# Robot.net
KiCad netlist of a schematic drawn in EAGLE
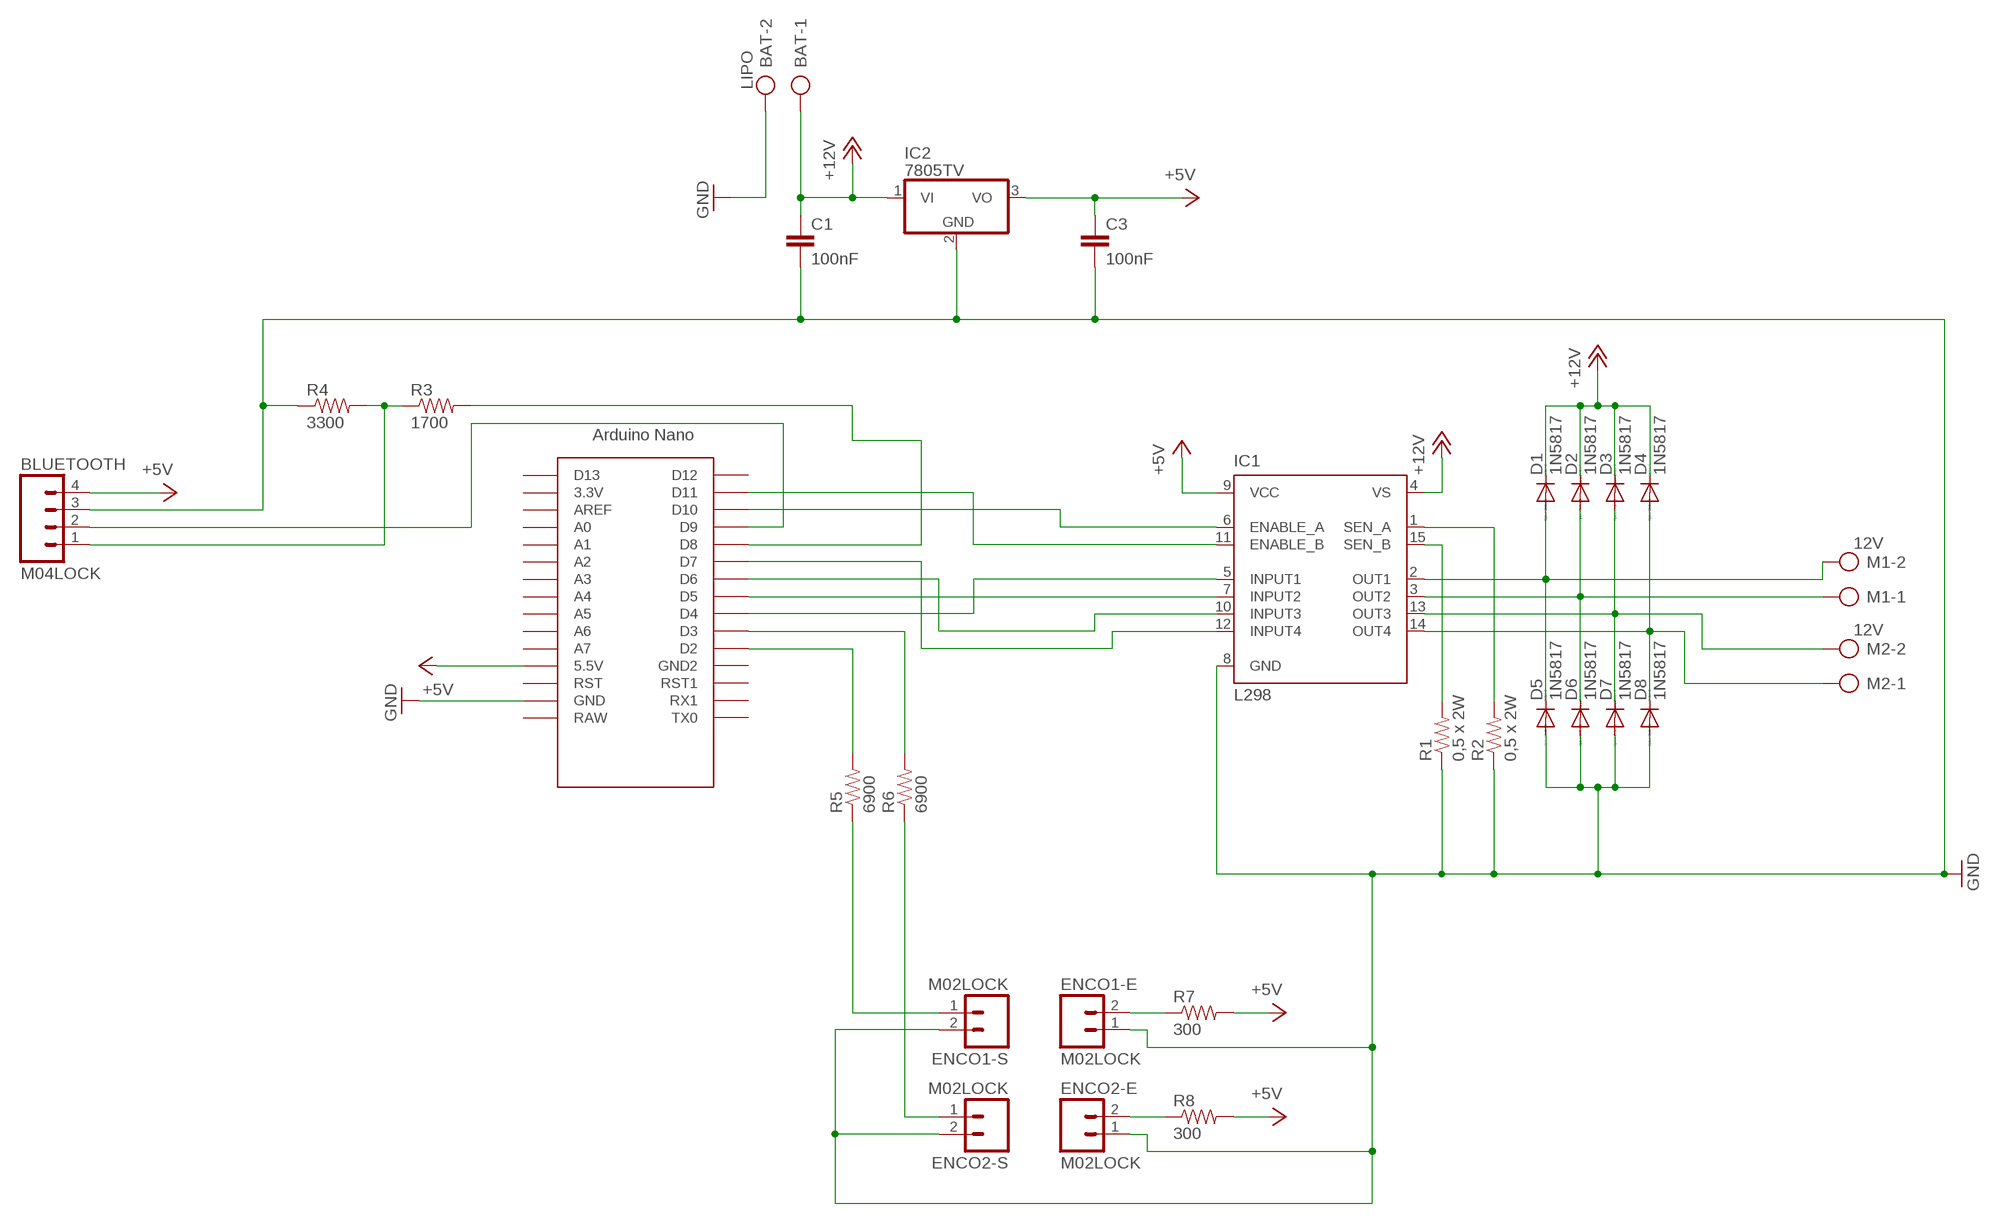
[diagram p0: schematic, sheet 1]

(export (version "E")
  (design (tool "Eeschema 10.0.6"))
  (components
    (comp (ref "BAT")
      (value "LIPO")
      (footprint "eagle-import:AK500_2-H")
      (libsource (lib "eagle-import") (part "AK500/2-H"))
    )
    (comp (ref "BLUETOOTH")
      (value "M04LOCK")
      (footprint "eagle-import:1X04_LOCK")
      (libsource (lib "eagle-import") (part "M04LOCK"))
    )
    (comp (ref "C1")
      (value "100nF")
      (footprint "eagle-import:C050-025X075")
      (libsource (lib "eagle-import") (part "C-EU050-025X075"))
    )
    (comp (ref "C3")
      (value "100nF")
      (footprint "eagle-import:C050-025X075")
      (libsource (lib "eagle-import") (part "C-EU050-025X075"))
    )
    (comp (ref "D1")
      (value "1N5817")
      (footprint "eagle-import:DO41-10")
      (libsource (lib "eagle-import") (part "1N4004"))
    )
    (comp (ref "D2")
      (value "1N5817")
      (footprint "eagle-import:DO41-10")
      (libsource (lib "eagle-import") (part "1N4004"))
    )
    (comp (ref "D3")
      (value "1N5817")
      (footprint "eagle-import:DO41-10")
      (libsource (lib "eagle-import") (part "1N4004"))
    )
    (comp (ref "D4")
      (value "1N5817")
      (footprint "eagle-import:DO41-10")
      (libsource (lib "eagle-import") (part "1N4004"))
    )
    (comp (ref "D5")
      (value "1N5817")
      (footprint "eagle-import:DO41-10")
      (libsource (lib "eagle-import") (part "1N4004"))
    )
    (comp (ref "D6")
      (value "1N5817")
      (footprint "eagle-import:DO41-10")
      (libsource (lib "eagle-import") (part "1N4004"))
    )
    (comp (ref "D7")
      (value "1N5817")
      (footprint "eagle-import:DO41-10")
      (libsource (lib "eagle-import") (part "1N4004"))
    )
    (comp (ref "D8")
      (value "1N5817")
      (footprint "eagle-import:DO41-10")
      (libsource (lib "eagle-import") (part "1N4004"))
    )
    (comp (ref "ENCO1-E")
      (value "M02LOCK")
      (footprint "eagle-import:1X02_LOCK")
      (libsource (lib "eagle-import") (part "M02LOCK"))
    )
    (comp (ref "ENCO1-S")
      (value "M02LOCK")
      (footprint "eagle-import:1X02_LOCK")
      (libsource (lib "eagle-import") (part "M02LOCK"))
    )
    (comp (ref "ENCO2-E")
      (value "M02LOCK")
      (footprint "eagle-import:1X02_LOCK")
      (libsource (lib "eagle-import") (part "M02LOCK"))
    )
    (comp (ref "ENCO2-S")
      (value "M02LOCK")
      (footprint "eagle-import:1X02_LOCK")
      (libsource (lib "eagle-import") (part "M02LOCK"))
    )
    (comp (ref "IC1")
      (value "L298")
      (footprint "eagle-import:MULTIWATT-15")
      (fields (field (name "MPN") "L298N"))
      (libsource (lib "eagle-import") (part "L298"))
    )
    (comp (ref "IC2")
      (value "7805TV")
      (footprint "eagle-import:TO220V")
      (libsource (lib "eagle-import") (part "78TV05"))
    )
    (comp (ref "M1")
      (value "12V")
      (footprint "eagle-import:AK500_2-H")
      (libsource (lib "eagle-import") (part "AK500/2-H"))
    )
    (comp (ref "M2")
      (value "12V")
      (footprint "eagle-import:AK500_2-H")
      (libsource (lib "eagle-import") (part "AK500/2-H"))
    )
    (comp (ref "R1")
      (value "0,5 x 2W")
      (footprint "eagle-import:AXIAL-0.5")
      (libsource (lib "eagle-import") (part "RESISTORPTH-1/2W"))
    )
    (comp (ref "R2")
      (value "0,5 x 2W")
      (footprint "eagle-import:AXIAL-0.5")
      (libsource (lib "eagle-import") (part "RESISTORPTH-1/2W"))
    )
    (comp (ref "R3")
      (value "1700")
      (footprint "eagle-import:AXIAL-0.3")
      (libsource (lib "eagle-import") (part "RESISTORAXIAL-0.3"))
    )
    (comp (ref "R4")
      (value "3300")
      (footprint "eagle-import:AXIAL-0.3")
      (libsource (lib "eagle-import") (part "RESISTORAXIAL-0.3"))
    )
    (comp (ref "R5")
      (value "6900")
      (footprint "eagle-import:AXIAL-0.3")
      (libsource (lib "eagle-import") (part "RESISTORAXIAL-0.3"))
    )
    (comp (ref "R6")
      (value "6900")
      (footprint "eagle-import:AXIAL-0.3")
      (libsource (lib "eagle-import") (part "RESISTORAXIAL-0.3"))
    )
    (comp (ref "R7")
      (value "300")
      (footprint "eagle-import:AXIAL-0.3")
      (libsource (lib "eagle-import") (part "RESISTORAXIAL-0.3"))
    )
    (comp (ref "R8")
      (value "300")
      (footprint "eagle-import:AXIAL-0.3")
      (libsource (lib "eagle-import") (part "RESISTORAXIAL-0.3"))
    )
    (comp (ref "U$1")
      (value "NANO")
      (footprint "eagle-import:NANO")
      (libsource (lib "eagle-import") (part "NANO"))
    )
  )
  (nets
    (net (code "1") (name "+5V") (class "Default")
      (node (ref "BLUETOOTH") (pin "4") (pinfunction "4_4") (pintype "passive"))
      (node (ref "C3") (pin "1") (pinfunction "1_1") (pintype "passive"))
      (node (ref "IC1") (pin "9") (pinfunction "VCC_9") (pintype "power_in"))
      (node (ref "IC2") (pin "3") (pinfunction "VO_3") (pintype "passive"))
      (node (ref "R7") (pin "P$2") (pinfunction "2_P$2") (pintype "passive"))
      (node (ref "R8") (pin "P$2") (pinfunction "2_P$2") (pintype "passive"))
      (node (ref "U$1") (pin "5V") (pinfunction "5.5V_5V") (pintype "bidirectional"))
    )
    (net (code "2") (name "+12V") (class "Default")
      (node (ref "BAT") (pin "1") (pinfunction "KL_1") (pintype "passive"))
      (node (ref "C1") (pin "1") (pinfunction "1_1") (pintype "passive"))
      (node (ref "D1") (pin "C") (pinfunction "C_C") (pintype "passive"))
      (node (ref "D2") (pin "C") (pinfunction "C_C") (pintype "passive"))
      (node (ref "D3") (pin "C") (pinfunction "C_C") (pintype "passive"))
      (node (ref "D4") (pin "C") (pinfunction "C_C") (pintype "passive"))
      (node (ref "IC1") (pin "4") (pinfunction "VS_4") (pintype "power_in"))
      (node (ref "IC2") (pin "1") (pinfunction "VI_1") (pintype "input"))
    )
    (net (code "3") (name "GND") (class "Default")
      (node (ref "BAT") (pin "2") (pinfunction "KL_2") (pintype "passive"))
      (node (ref "BLUETOOTH") (pin "3") (pinfunction "3_3") (pintype "passive"))
      (node (ref "C1") (pin "2") (pinfunction "2_2") (pintype "passive"))
      (node (ref "C3") (pin "2") (pinfunction "2_2") (pintype "passive"))
      (node (ref "D5") (pin "A") (pinfunction "A_A") (pintype "passive"))
      (node (ref "D6") (pin "A") (pinfunction "A_A") (pintype "passive"))
      (node (ref "D7") (pin "A") (pinfunction "A_A") (pintype "passive"))
      (node (ref "D8") (pin "A") (pinfunction "A_A") (pintype "passive"))
      (node (ref "ENCO1-E") (pin "1") (pinfunction "1_1") (pintype "passive"))
      (node (ref "ENCO1-S") (pin "2") (pinfunction "2_2") (pintype "passive"))
      (node (ref "ENCO2-E") (pin "1") (pinfunction "1_1") (pintype "passive"))
      (node (ref "ENCO2-S") (pin "2") (pinfunction "2_2") (pintype "passive"))
      (node (ref "IC1") (pin "8") (pinfunction "GND_8") (pintype "power_in"))
      (node (ref "IC2") (pin "2") (pinfunction "GND_2") (pintype "passive"))
      (node (ref "R1") (pin "P$1") (pinfunction "1_P$1") (pintype "passive"))
      (node (ref "R2") (pin "P$1") (pinfunction "1_P$1") (pintype "passive"))
      (node (ref "R4") (pin "P$1") (pinfunction "1_P$1") (pintype "passive"))
      (node (ref "U$1") (pin "GND") (pinfunction "GND_GND") (pintype "bidirectional"))
    )
    (net (code "4") (name "Net-(BLUETOOTH-Pad2)") (class "Default")
      (node (ref "BLUETOOTH") (pin "2") (pinfunction "2_2") (pintype "passive"))
      (node (ref "U$1") (pin "D9") (pinfunction "D9_D9") (pintype "bidirectional"))
    )
    (net (code "5") (name "Net-(IC1-ENABLE_A)") (class "Default")
      (node (ref "IC1") (pin "6") (pinfunction "ENABLE_A_6") (pintype "input"))
      (node (ref "U$1") (pin "D10") (pinfunction "D10_D10") (pintype "bidirectional"))
    )
    (net (code "6") (name "Net-(IC1-ENABLE_B)") (class "Default")
      (node (ref "IC1") (pin "11") (pinfunction "ENABLE_B_11") (pintype "input"))
      (node (ref "U$1") (pin "D11") (pinfunction "D11_D11") (pintype "bidirectional"))
    )
    (net (code "7") (name "Net-(IC1-INPUT1)") (class "Default")
      (node (ref "IC1") (pin "5") (pinfunction "INPUT1_5") (pintype "input"))
      (node (ref "U$1") (pin "D4") (pinfunction "D4_D4") (pintype "bidirectional"))
    )
    (net (code "8") (name "Net-(IC1-INPUT2)") (class "Default")
      (node (ref "IC1") (pin "7") (pinfunction "INPUT2_7") (pintype "input"))
      (node (ref "U$1") (pin "D5") (pinfunction "D5_D5") (pintype "bidirectional"))
    )
    (net (code "9") (name "Net-(IC1-INPUT3)") (class "Default")
      (node (ref "IC1") (pin "10") (pinfunction "INPUT3_10") (pintype "input"))
      (node (ref "U$1") (pin "D6") (pinfunction "D6_D6") (pintype "bidirectional"))
    )
    (net (code "10") (name "Net-(IC1-INPUT4)") (class "Default")
      (node (ref "IC1") (pin "12") (pinfunction "INPUT4_12") (pintype "input"))
      (node (ref "U$1") (pin "D7") (pinfunction "D7_D7") (pintype "bidirectional"))
    )
    (net (code "11") (name "Net-(IC1-OUT1)") (class "Default")
      (node (ref "D1") (pin "A") (pinfunction "A_A") (pintype "passive"))
      (node (ref "D5") (pin "C") (pinfunction "C_C") (pintype "passive"))
      (node (ref "IC1") (pin "2") (pinfunction "OUT1_2") (pintype "output"))
      (node (ref "M1") (pin "2") (pinfunction "KL_2") (pintype "passive"))
    )
    (net (code "12") (name "Net-(IC1-OUT2)") (class "Default")
      (node (ref "D2") (pin "A") (pinfunction "A_A") (pintype "passive"))
      (node (ref "D6") (pin "C") (pinfunction "C_C") (pintype "passive"))
      (node (ref "IC1") (pin "3") (pinfunction "OUT2_3") (pintype "output"))
      (node (ref "M1") (pin "1") (pinfunction "KL_1") (pintype "passive"))
    )
    (net (code "13") (name "Net-(IC1-OUT3)") (class "Default")
      (node (ref "D3") (pin "A") (pinfunction "A_A") (pintype "passive"))
      (node (ref "D7") (pin "C") (pinfunction "C_C") (pintype "passive"))
      (node (ref "IC1") (pin "13") (pinfunction "OUT3_13") (pintype "output"))
      (node (ref "M2") (pin "2") (pinfunction "KL_2") (pintype "passive"))
    )
    (net (code "14") (name "Net-(IC1-OUT4)") (class "Default")
      (node (ref "D4") (pin "A") (pinfunction "A_A") (pintype "passive"))
      (node (ref "D8") (pin "C") (pinfunction "C_C") (pintype "passive"))
      (node (ref "IC1") (pin "14") (pinfunction "OUT4_14") (pintype "output"))
      (node (ref "M2") (pin "1") (pinfunction "KL_1") (pintype "passive"))
    )
    (net (code "15") (name "Net-(IC1-SEN_A)") (class "Default")
      (node (ref "IC1") (pin "1") (pinfunction "SEN_A_1") (pintype "input"))
      (node (ref "R2") (pin "P$2") (pinfunction "2_P$2") (pintype "passive"))
    )
    (net (code "16") (name "Net-(IC1-SEN_B)") (class "Default")
      (node (ref "IC1") (pin "15") (pinfunction "SEN_B_15") (pintype "input"))
      (node (ref "R1") (pin "P$2") (pinfunction "2_P$2") (pintype "passive"))
    )
    (net (code "17") (name "Net-(R3-1)") (class "Default")
      (node (ref "BLUETOOTH") (pin "1") (pinfunction "1_1") (pintype "passive"))
      (node (ref "R3") (pin "P$1") (pinfunction "1_P$1") (pintype "passive"))
      (node (ref "R4") (pin "P$2") (pinfunction "2_P$2") (pintype "passive"))
    )
    (net (code "18") (name "Net-(R3-2)") (class "Default")
      (node (ref "R3") (pin "P$2") (pinfunction "2_P$2") (pintype "passive"))
      (node (ref "U$1") (pin "D8") (pinfunction "D8_D8") (pintype "bidirectional"))
    )
    (net (code "19") (name "Net-(R5-1)") (class "Default")
      (node (ref "ENCO1-S") (pin "1") (pinfunction "1_1") (pintype "passive"))
      (node (ref "R5") (pin "P$1") (pinfunction "1_P$1") (pintype "passive"))
    )
    (net (code "20") (name "Net-(R5-2)") (class "Default")
      (node (ref "R5") (pin "P$2") (pinfunction "2_P$2") (pintype "passive"))
      (node (ref "U$1") (pin "D2") (pinfunction "D2_D2") (pintype "bidirectional"))
    )
    (net (code "21") (name "Net-(R6-1)") (class "Default")
      (node (ref "ENCO2-S") (pin "1") (pinfunction "1_1") (pintype "passive"))
      (node (ref "R6") (pin "P$1") (pinfunction "1_P$1") (pintype "passive"))
    )
    (net (code "22") (name "Net-(R6-2)") (class "Default")
      (node (ref "R6") (pin "P$2") (pinfunction "2_P$2") (pintype "passive"))
      (node (ref "U$1") (pin "D3") (pinfunction "D3_D3") (pintype "bidirectional"))
    )
    (net (code "23") (name "Net-(R7-1)") (class "Default")
      (node (ref "ENCO1-E") (pin "2") (pinfunction "2_2") (pintype "passive"))
      (node (ref "R7") (pin "P$1") (pinfunction "1_P$1") (pintype "passive"))
    )
    (net (code "24") (name "Net-(R8-1)") (class "Default")
      (node (ref "ENCO2-E") (pin "2") (pinfunction "2_2") (pintype "passive"))
      (node (ref "R8") (pin "P$1") (pinfunction "1_P$1") (pintype "passive"))
    )
    (net (code "25") (name "unconnected-(U$1-GND2-PadGND1)") (class "Default")
      (node (ref "U$1") (pin "GND1") (pinfunction "GND2_GND1") (pintype "bidirectional"))
    )
    (net (code "26") (name "unconnected-(U$1-Pad3.3V)") (class "Default")
      (node (ref "U$1") (pin "3.3V") (pinfunction "3.3V_3.3V") (pintype "bidirectional"))
    )
    (net (code "27") (name "unconnected-(U$1-PadA0)") (class "Default")
      (node (ref "U$1") (pin "A0") (pinfunction "A0_A0") (pintype "bidirectional"))
    )
    (net (code "28") (name "unconnected-(U$1-PadA1)") (class "Default")
      (node (ref "U$1") (pin "A1") (pinfunction "A1_A1") (pintype "bidirectional"))
    )
    (net (code "29") (name "unconnected-(U$1-PadA2)") (class "Default")
      (node (ref "U$1") (pin "A2") (pinfunction "A2_A2") (pintype "bidirectional"))
    )
    (net (code "30") (name "unconnected-(U$1-PadA3)") (class "Default")
      (node (ref "U$1") (pin "A3") (pinfunction "A3_A3") (pintype "bidirectional"))
    )
    (net (code "31") (name "unconnected-(U$1-PadA4)") (class "Default")
      (node (ref "U$1") (pin "A4") (pinfunction "A4_A4") (pintype "bidirectional"))
    )
    (net (code "32") (name "unconnected-(U$1-PadA5)") (class "Default")
      (node (ref "U$1") (pin "A5") (pinfunction "A5_A5") (pintype "bidirectional"))
    )
    (net (code "33") (name "unconnected-(U$1-PadA6)") (class "Default")
      (node (ref "U$1") (pin "A6") (pinfunction "A6_A6") (pintype "bidirectional"))
    )
    (net (code "34") (name "unconnected-(U$1-PadA7)") (class "Default")
      (node (ref "U$1") (pin "A7") (pinfunction "A7_A7") (pintype "bidirectional"))
    )
    (net (code "35") (name "unconnected-(U$1-PadAREF)") (class "Default")
      (node (ref "U$1") (pin "AREF") (pinfunction "AREF_AREF") (pintype "bidirectional"))
    )
    (net (code "36") (name "unconnected-(U$1-PadD12)") (class "Default")
      (node (ref "U$1") (pin "D12") (pinfunction "D12_D12") (pintype "bidirectional"))
    )
    (net (code "37") (name "unconnected-(U$1-PadD13)") (class "Default")
      (node (ref "U$1") (pin "D13") (pinfunction "D13_D13") (pintype "bidirectional"))
    )
    (net (code "38") (name "unconnected-(U$1-PadICSP1)") (class "Default")
      (node (ref "U$1") (pin "ICSP1") (pinfunction "ICSP1_ICSP1") (pintype "bidirectional"))
    )
    (net (code "39") (name "unconnected-(U$1-PadICSP2)") (class "Default")
      (node (ref "U$1") (pin "ICSP2") (pinfunction "ICSP2_ICSP2") (pintype "bidirectional"))
    )
    (net (code "40") (name "unconnected-(U$1-PadICSP3)") (class "Default")
      (node (ref "U$1") (pin "ICSP3") (pinfunction "ICSP3_ICSP3") (pintype "bidirectional"))
    )
    (net (code "41") (name "unconnected-(U$1-PadICSP4)") (class "Default")
      (node (ref "U$1") (pin "ICSP4") (pinfunction "ICSP4_ICSP4") (pintype "bidirectional"))
    )
    (net (code "42") (name "unconnected-(U$1-PadICSP5)") (class "Default")
      (node (ref "U$1") (pin "ICSP5") (pinfunction "ICSP5_ICSP5") (pintype "bidirectional"))
    )
    (net (code "43") (name "unconnected-(U$1-PadICSP6)") (class "Default")
      (node (ref "U$1") (pin "ICSP6") (pinfunction "ICSP6_ICSP6") (pintype "bidirectional"))
    )
    (net (code "44") (name "unconnected-(U$1-PadRAW)") (class "Default")
      (node (ref "U$1") (pin "RAW") (pinfunction "RAW_RAW") (pintype "bidirectional"))
    )
    (net (code "45") (name "unconnected-(U$1-PadRST)") (class "Default")
      (node (ref "U$1") (pin "RST") (pinfunction "RST_RST") (pintype "bidirectional"))
    )
    (net (code "46") (name "unconnected-(U$1-PadRST1)") (class "Default")
      (node (ref "U$1") (pin "RST1") (pinfunction "RST1_RST1") (pintype "bidirectional"))
    )
    (net (code "47") (name "unconnected-(U$1-PadRX1)") (class "Default")
      (node (ref "U$1") (pin "RX1") (pinfunction "RX1_RX1") (pintype "bidirectional"))
    )
    (net (code "48") (name "unconnected-(U$1-PadTX0)") (class "Default")
      (node (ref "U$1") (pin "TX0") (pinfunction "TX0_TX0") (pintype "bidirectional"))
    )
  )
)
